# pcf8574-breakout.net
KiCad netlist of a schematic drawn in EAGLE
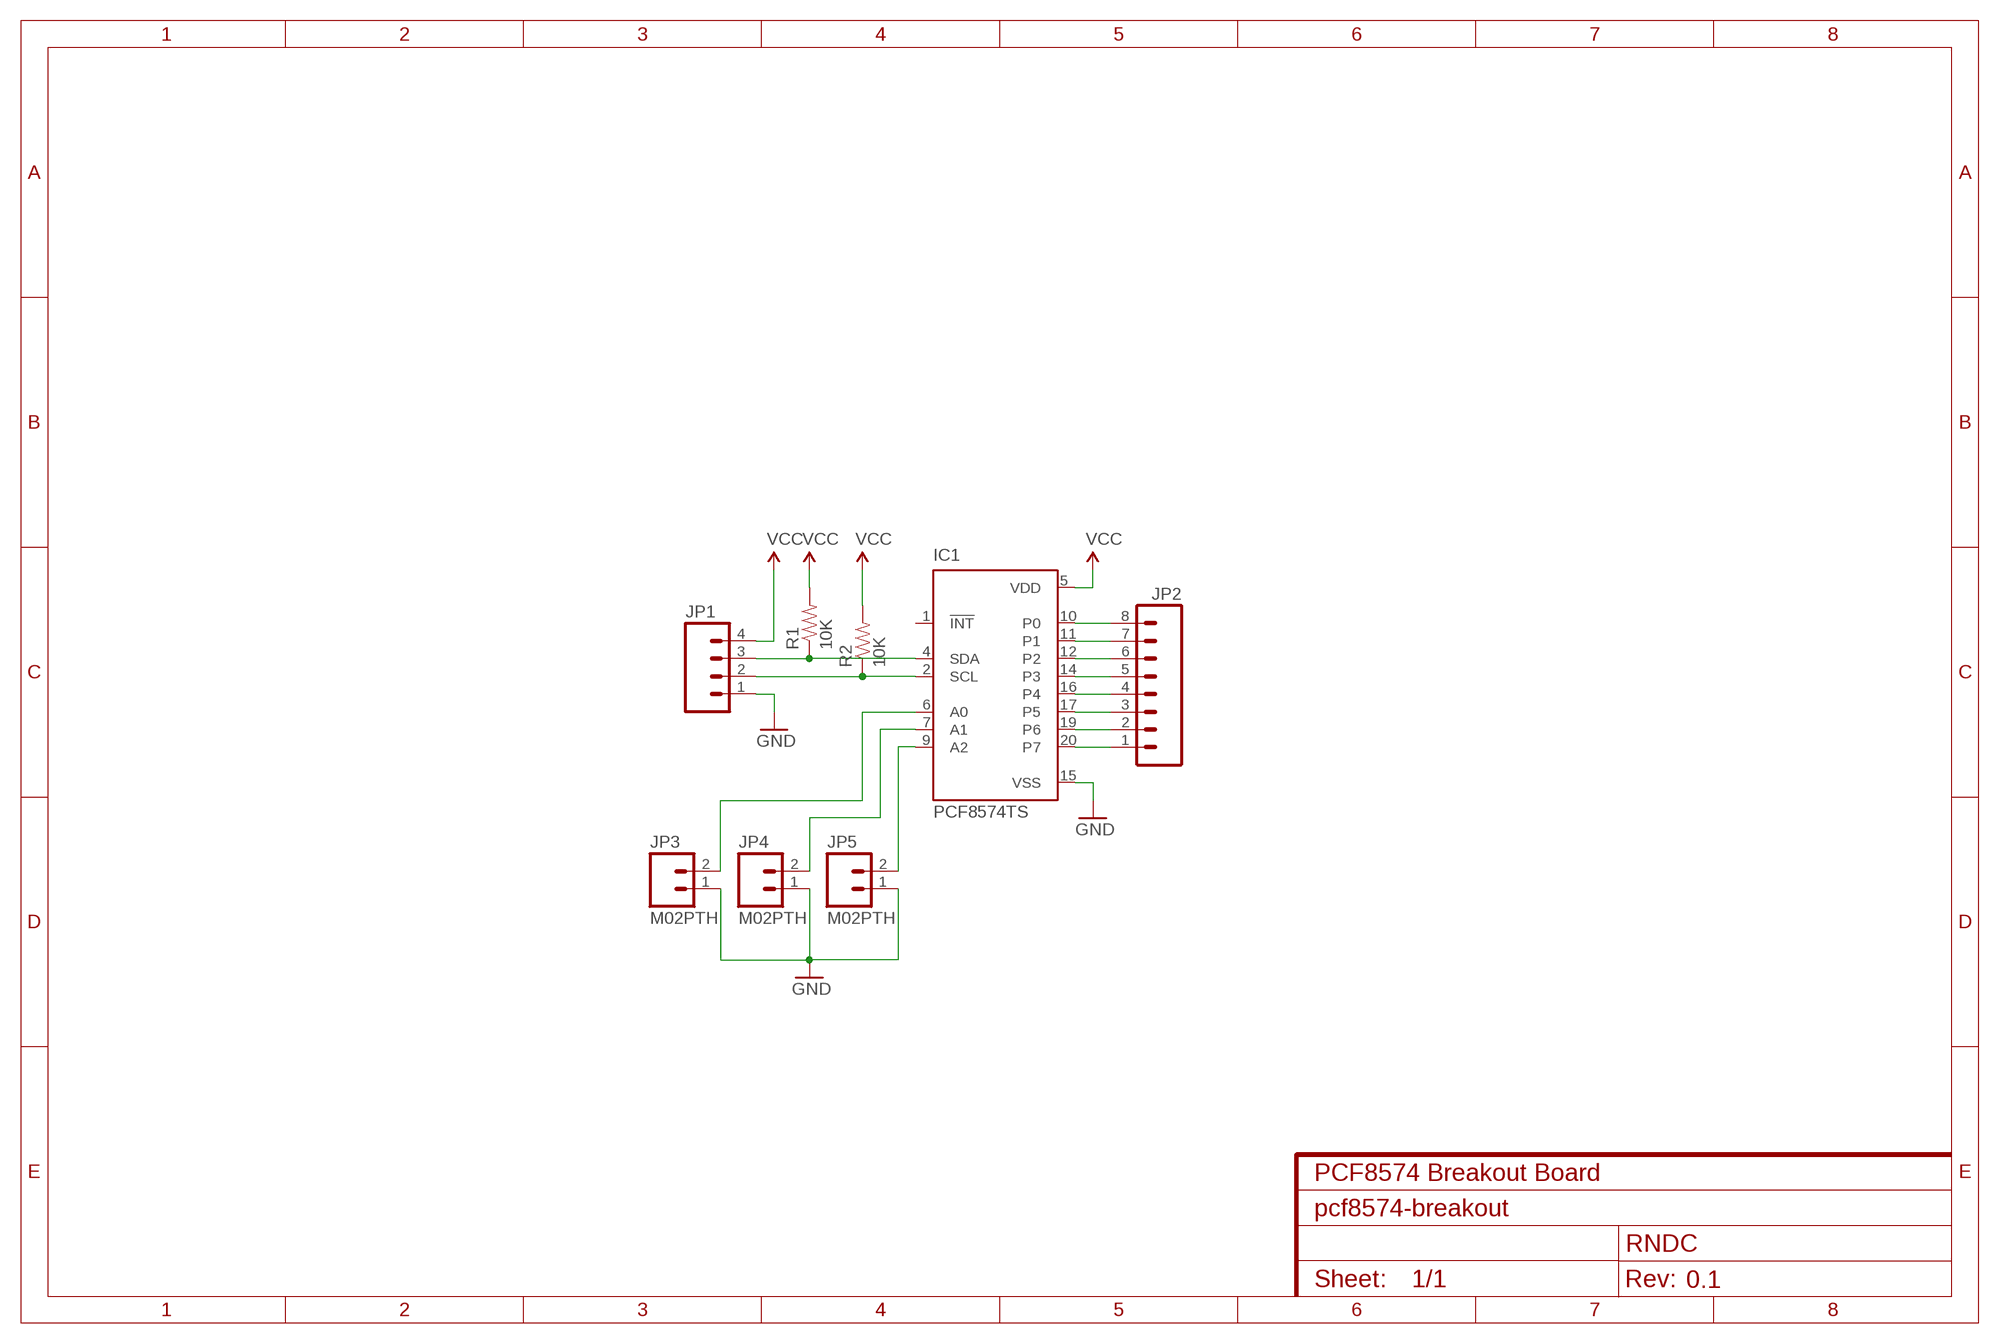
[diagram p0: schematic, sheet 1]

(export (version "E")
  (design (tool "Eeschema 10.0.6"))
  (components
    (comp (ref "IC1")
      (value "PCF8574TS")
      (footprint "eagle-import:SSOP20")
      (fields (field (name "MPN") "PCF8574TS/3,118"))
      (libsource (lib "eagle-import") (part "PCF8574TS"))
    )
    (comp (ref "JP1")
      (value "M04PTH")
      (footprint "eagle-import:1X04")
      (libsource (lib "eagle-import") (part "M04PTH"))
    )
    (comp (ref "JP2")
      (value "M081X08")
      (footprint "eagle-import:1X08")
      (libsource (lib "eagle-import") (part "M081X08"))
    )
    (comp (ref "JP3")
      (value "M02PTH")
      (footprint "eagle-import:1X02")
      (libsource (lib "eagle-import") (part "M02PTH"))
    )
    (comp (ref "JP4")
      (value "M02PTH")
      (footprint "eagle-import:1X02")
      (libsource (lib "eagle-import") (part "M02PTH"))
    )
    (comp (ref "JP5")
      (value "M02PTH")
      (footprint "eagle-import:1X02")
      (libsource (lib "eagle-import") (part "M02PTH"))
    )
    (comp (ref "R1")
      (value "10K")
      (footprint "eagle-import:0603-RES")
      (libsource (lib "eagle-import") (part "RESISTOR0603-RES"))
    )
    (comp (ref "R2")
      (value "10K")
      (footprint "eagle-import:0603-RES")
      (libsource (lib "eagle-import") (part "RESISTOR0603-RES"))
    )
  )
  (nets
    (net (code "1") (name "GND") (class "Default")
      (node (ref "IC1") (pin "15") (pinfunction "VSS_15") (pintype "power_in"))
      (node (ref "JP1") (pin "1") (pinfunction "1_1") (pintype "passive"))
      (node (ref "JP3") (pin "1") (pinfunction "1_1") (pintype "passive"))
      (node (ref "JP4") (pin "1") (pinfunction "1_1") (pintype "passive"))
      (node (ref "JP5") (pin "1") (pinfunction "1_1") (pintype "passive"))
    )
    (net (code "2") (name "Net-(IC1-A0)") (class "Default")
      (node (ref "IC1") (pin "6") (pinfunction "A0_6") (pintype "input"))
      (node (ref "JP3") (pin "2") (pinfunction "2_2") (pintype "passive"))
    )
    (net (code "3") (name "Net-(IC1-A1)") (class "Default")
      (node (ref "IC1") (pin "7") (pinfunction "A1_7") (pintype "input"))
      (node (ref "JP4") (pin "2") (pinfunction "2_2") (pintype "passive"))
    )
    (net (code "4") (name "Net-(IC1-A2)") (class "Default")
      (node (ref "IC1") (pin "9") (pinfunction "A2_9") (pintype "input"))
      (node (ref "JP5") (pin "2") (pinfunction "2_2") (pintype "passive"))
    )
    (net (code "5") (name "Net-(IC1-P0)") (class "Default")
      (node (ref "IC1") (pin "10") (pinfunction "P0_10") (pintype "bidirectional"))
      (node (ref "JP2") (pin "8") (pinfunction "8_8") (pintype "passive"))
    )
    (net (code "6") (name "Net-(IC1-P1)") (class "Default")
      (node (ref "IC1") (pin "11") (pinfunction "P1_11") (pintype "bidirectional"))
      (node (ref "JP2") (pin "7") (pinfunction "7_7") (pintype "passive"))
    )
    (net (code "7") (name "Net-(IC1-P2)") (class "Default")
      (node (ref "IC1") (pin "12") (pinfunction "P2_12") (pintype "bidirectional"))
      (node (ref "JP2") (pin "6") (pinfunction "6_6") (pintype "passive"))
    )
    (net (code "8") (name "Net-(IC1-P3)") (class "Default")
      (node (ref "IC1") (pin "14") (pinfunction "P3_14") (pintype "bidirectional"))
      (node (ref "JP2") (pin "5") (pinfunction "5_5") (pintype "passive"))
    )
    (net (code "9") (name "Net-(IC1-P4)") (class "Default")
      (node (ref "IC1") (pin "16") (pinfunction "P4_16") (pintype "bidirectional"))
      (node (ref "JP2") (pin "4") (pinfunction "4_4") (pintype "passive"))
    )
    (net (code "10") (name "Net-(IC1-P5)") (class "Default")
      (node (ref "IC1") (pin "17") (pinfunction "P5_17") (pintype "bidirectional"))
      (node (ref "JP2") (pin "3") (pinfunction "3_3") (pintype "passive"))
    )
    (net (code "11") (name "Net-(IC1-P6)") (class "Default")
      (node (ref "IC1") (pin "19") (pinfunction "P6_19") (pintype "bidirectional"))
      (node (ref "JP2") (pin "2") (pinfunction "2_2") (pintype "passive"))
    )
    (net (code "12") (name "Net-(IC1-P7)") (class "Default")
      (node (ref "IC1") (pin "20") (pinfunction "P7_20") (pintype "bidirectional"))
      (node (ref "JP2") (pin "1") (pinfunction "1_1") (pintype "passive"))
    )
    (net (code "13") (name "Net-(IC1-SCL)") (class "Default")
      (node (ref "IC1") (pin "2") (pinfunction "SCL_2") (pintype "input"))
      (node (ref "JP1") (pin "2") (pinfunction "2_2") (pintype "passive"))
      (node (ref "R2") (pin "1") (pinfunction "1_1") (pintype "passive"))
    )
    (net (code "14") (name "Net-(IC1-SDA)") (class "Default")
      (node (ref "IC1") (pin "4") (pinfunction "SDA_4") (pintype "bidirectional"))
      (node (ref "JP1") (pin "3") (pinfunction "3_3") (pintype "passive"))
      (node (ref "R1") (pin "1") (pinfunction "1_1") (pintype "passive"))
    )
    (net (code "15") (name "VCC") (class "Default")
      (node (ref "IC1") (pin "5") (pinfunction "VDD_5") (pintype "power_in"))
      (node (ref "JP1") (pin "4") (pinfunction "4_4") (pintype "passive"))
      (node (ref "R1") (pin "2") (pinfunction "2_2") (pintype "passive"))
      (node (ref "R2") (pin "2") (pinfunction "2_2") (pintype "passive"))
    )
    (net (code "16") (name "unconnected-(IC1-~{INT}-Pad1)") (class "Default")
      (node (ref "IC1") (pin "1") (pinfunction "~{INT}_1") (pintype "output"))
    )
  )
)
